# arcade_controls.net
KiCad netlist of a schematic drawn in EAGLE
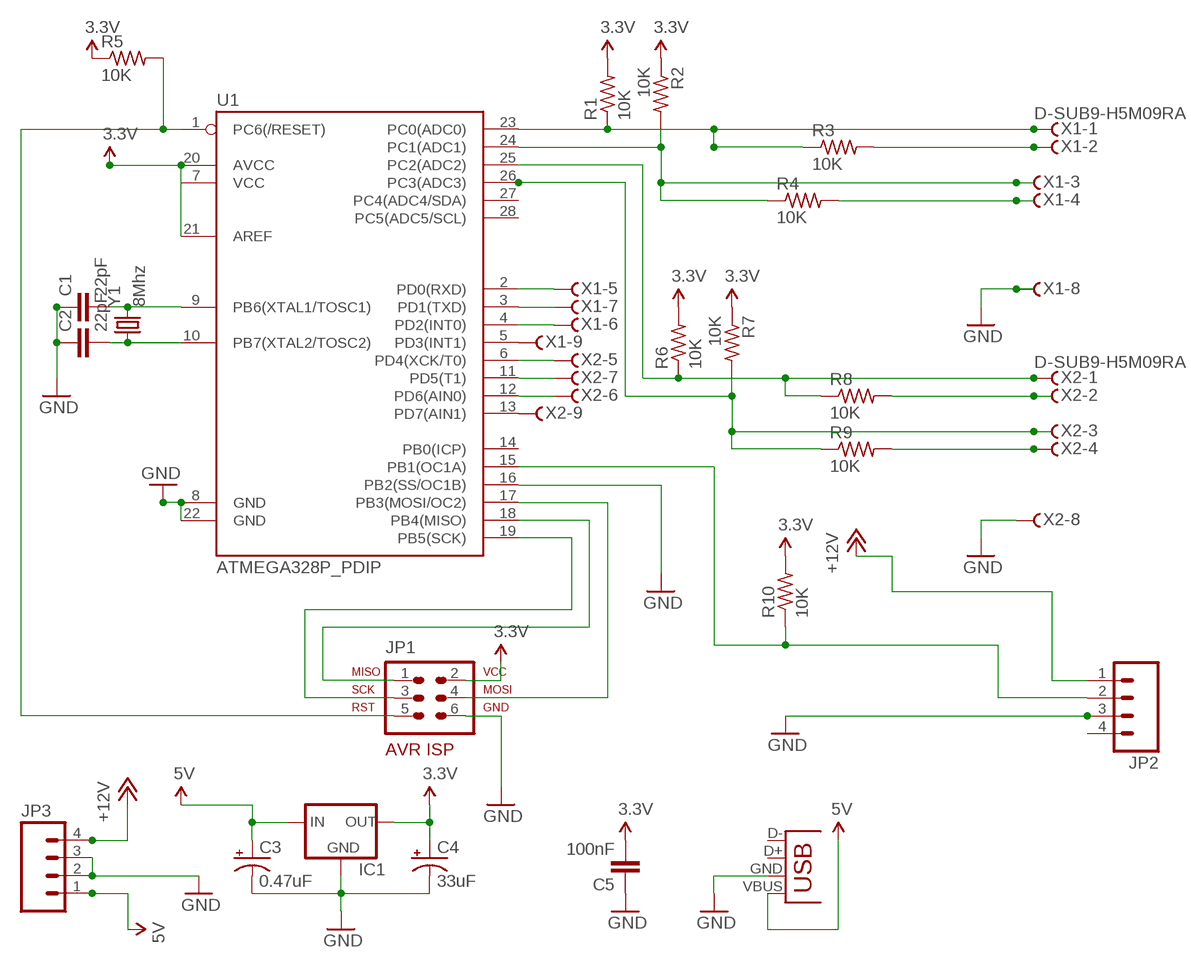
[diagram p0: schematic, sheet 1]

(export (version "E")
  (design (tool "Eeschema 10.0.6"))
  (components
    (comp (ref "C1")
      (value "22pF")
      (footprint "eagle-import:CAP-PTH-SMALL")
      (libsource (lib "eagle-import") (part "CAPPTH"))
    )
    (comp (ref "C2")
      (value "22pF")
      (footprint "eagle-import:CAP-PTH-SMALL")
      (libsource (lib "eagle-import") (part "CAPPTH"))
    )
    (comp (ref "C3")
      (value "0.47uF")
      (footprint "eagle-import:CPOL-RADIAL-10UF-25V")
      (libsource (lib "eagle-import") (part "CAP_POLPTH2"))
    )
    (comp (ref "C4")
      (value "33uF")
      (footprint "eagle-import:CPOL-RADIAL-10UF-25V")
      (libsource (lib "eagle-import") (part "CAP_POLPTH2"))
    )
    (comp (ref "C5")
      (value "100nF")
      (footprint "eagle-import:CAP-PTH-SMALL")
      (libsource (lib "eagle-import") (part "CAPPTH"))
    )
    (comp (ref "IC1")
      (value "V_REG_78XXSIDE")
      (footprint "eagle-import:78XXL")
      (libsource (lib "eagle-import") (part "V_REG_78XXSIDE"))
    )
    (comp (ref "JP1")
      (value "AVR-ISP-6VERT")
      (footprint "eagle-import:AVR-ISP-6")
      (libsource (lib "eagle-import") (part "AVR-ISP-6VERT"))
    )
    (comp (ref "JP2")
      (value "M04LOCK")
      (footprint "eagle-import:1X04_LOCK")
      (libsource (lib "eagle-import") (part "M04LOCK"))
    )
    (comp (ref "JP3")
      (value "M04LOCK")
      (footprint "eagle-import:1X04_LOCK")
      (libsource (lib "eagle-import") (part "M04LOCK"))
    )
    (comp (ref "JP4")
      (value "USB-A-H")
      (footprint "eagle-import:USB-A-H")
      (libsource (lib "eagle-import") (part "USB-A-H"))
    )
    (comp (ref "R1")
      (value "10K")
      (footprint "eagle-import:0309_12")
      (libsource (lib "eagle-import") (part "R-US_0309/12"))
    )
    (comp (ref "R2")
      (value "10K")
      (footprint "eagle-import:0309_12")
      (libsource (lib "eagle-import") (part "R-US_0309/12"))
    )
    (comp (ref "R3")
      (value "10K")
      (footprint "eagle-import:0309_12")
      (libsource (lib "eagle-import") (part "R-US_0309/12"))
    )
    (comp (ref "R4")
      (value "10K")
      (footprint "eagle-import:0309_12")
      (libsource (lib "eagle-import") (part "R-US_0309/12"))
    )
    (comp (ref "R5")
      (value "10K")
      (footprint "eagle-import:0309_12")
      (libsource (lib "eagle-import") (part "R-US_0309/12"))
    )
    (comp (ref "R6")
      (value "10K")
      (footprint "eagle-import:0309_12")
      (libsource (lib "eagle-import") (part "R-US_0309/12"))
    )
    (comp (ref "R7")
      (value "10K")
      (footprint "eagle-import:0309_12")
      (libsource (lib "eagle-import") (part "R-US_0309/12"))
    )
    (comp (ref "R8")
      (value "10K")
      (footprint "eagle-import:0309_12")
      (libsource (lib "eagle-import") (part "R-US_0309/12"))
    )
    (comp (ref "R9")
      (value "10K")
      (footprint "eagle-import:0309_12")
      (libsource (lib "eagle-import") (part "R-US_0309/12"))
    )
    (comp (ref "R10")
      (value "10K")
      (footprint "eagle-import:0309_12")
      (libsource (lib "eagle-import") (part "R-US_0309/12"))
    )
    (comp (ref "U1")
      (value "ATMEGA328P_PDIP")
      (footprint "eagle-import:DIL28-3")
      (libsource (lib "eagle-import") (part "ATMEGA328P_PDIP"))
    )
    (comp (ref "X1")
      (value "D-SUB9-H5M09RA")
      (footprint "eagle-import:H5M09RA")
      (libsource (lib "eagle-import") (part "D-SUB9-H5M09RA"))
    )
    (comp (ref "X2")
      (value "D-SUB9-H5M09RA")
      (footprint "eagle-import:H5M09RA")
      (libsource (lib "eagle-import") (part "D-SUB9-H5M09RA"))
    )
    (comp (ref "Y1")
      (value "8Mhz")
      (footprint "eagle-import:HC49U-V")
      (libsource (lib "eagle-import") (part "CRYSTALHC49UV"))
    )
  )
  (nets
    (net (code "1") (name "+12V") (class "Default")
      (node (ref "JP2") (pin "1") (pinfunction "1_1") (pintype "passive"))
      (node (ref "JP3") (pin "4") (pinfunction "4_4") (pintype "passive"))
    )
    (net (code "2") (name "3.3V") (class "Default")
      (node (ref "C4") (pin "1") (pinfunction "+_1") (pintype "passive"))
      (node (ref "C5") (pin "2") (pinfunction "2_2") (pintype "passive"))
      (node (ref "IC1") (pin "OUT") (pinfunction "OUT_OUT") (pintype "output"))
      (node (ref "JP1") (pin "2") (pinfunction "2_2") (pintype "passive"))
      (node (ref "R1") (pin "2") (pinfunction "2_2") (pintype "passive"))
      (node (ref "R10") (pin "2") (pinfunction "2_2") (pintype "passive"))
      (node (ref "R2") (pin "1") (pinfunction "1_1") (pintype "passive"))
      (node (ref "R5") (pin "1") (pinfunction "1_1") (pintype "passive"))
      (node (ref "R6") (pin "2") (pinfunction "2_2") (pintype "passive"))
      (node (ref "R7") (pin "1") (pinfunction "1_1") (pintype "passive"))
      (node (ref "U1") (pin "20") (pinfunction "AVCC_20") (pintype "bidirectional"))
      (node (ref "U1") (pin "21") (pinfunction "AREF_21") (pintype "bidirectional"))
      (node (ref "U1") (pin "7") (pinfunction "VCC_7") (pintype "bidirectional"))
    )
    (net (code "3") (name "5V") (class "Default")
      (node (ref "C3") (pin "1") (pinfunction "+_1") (pintype "passive"))
      (node (ref "IC1") (pin "IN") (pinfunction "IN_IN") (pintype "input"))
      (node (ref "JP3") (pin "1") (pinfunction "1_1") (pintype "passive"))
      (node (ref "JP4") (pin "VBUS") (pinfunction "GND_VBUS") (pintype "bidirectional"))
    )
    (net (code "4") (name "GND") (class "Default")
      (node (ref "C1") (pin "1") (pinfunction "1_1") (pintype "passive"))
      (node (ref "C2") (pin "1") (pinfunction "1_1") (pintype "passive"))
      (node (ref "C3") (pin "2") (pinfunction "-_2") (pintype "passive"))
      (node (ref "C4") (pin "2") (pinfunction "-_2") (pintype "passive"))
      (node (ref "C5") (pin "1") (pinfunction "1_1") (pintype "passive"))
      (node (ref "IC1") (pin "GND") (pinfunction "GND_GND") (pintype "input"))
      (node (ref "JP1") (pin "6") (pinfunction "6_6") (pintype "passive"))
      (node (ref "JP2") (pin "3") (pinfunction "3_3") (pintype "passive"))
      (node (ref "JP3") (pin "2") (pinfunction "2_2") (pintype "passive"))
      (node (ref "JP3") (pin "3") (pinfunction "3_3") (pintype "passive"))
      (node (ref "JP4") (pin "GND") (pinfunction "VBUS_GND") (pintype "bidirectional"))
      (node (ref "U1") (pin "16") (pinfunction "PB2(SS/OC1B)_16") (pintype "bidirectional"))
      (node (ref "U1") (pin "22") (pinfunction "GND_22") (pintype "bidirectional"))
      (node (ref "U1") (pin "8") (pinfunction "GND_8") (pintype "bidirectional"))
      (node (ref "X1") (pin "8") (pinfunction "F_8") (pintype "passive"))
      (node (ref "X2") (pin "8") (pinfunction "F_8") (pintype "passive"))
    )
    (net (code "5") (name "Net-(U1-PB1(OC1A))") (class "Default")
      (node (ref "JP2") (pin "2") (pinfunction "2_2") (pintype "passive"))
      (node (ref "R10") (pin "1") (pinfunction "1_1") (pintype "passive"))
      (node (ref "U1") (pin "15") (pinfunction "PB1(OC1A)_15") (pintype "bidirectional"))
    )
    (net (code "6") (name "Net-(U1-PB3(MOSI{slash}OC2))") (class "Default")
      (node (ref "JP1") (pin "4") (pinfunction "4_4") (pintype "passive"))
      (node (ref "U1") (pin "17") (pinfunction "PB3(MOSI/OC2)_17") (pintype "bidirectional"))
    )
    (net (code "7") (name "Net-(U1-PB4(MISO))") (class "Default")
      (node (ref "JP1") (pin "1") (pinfunction "1_1") (pintype "passive"))
      (node (ref "U1") (pin "18") (pinfunction "PB4(MISO)_18") (pintype "bidirectional"))
    )
    (net (code "8") (name "Net-(U1-PB5(SCK))") (class "Default")
      (node (ref "JP1") (pin "3") (pinfunction "3_3") (pintype "passive"))
      (node (ref "U1") (pin "19") (pinfunction "PB5(SCK)_19") (pintype "bidirectional"))
    )
    (net (code "9") (name "Net-(U1-PB6(XTAL1{slash}TOSC1))") (class "Default")
      (node (ref "C1") (pin "2") (pinfunction "2_2") (pintype "passive"))
      (node (ref "U1") (pin "9") (pinfunction "PB6(XTAL1/TOSC1)_9") (pintype "bidirectional"))
      (node (ref "Y1") (pin "2") (pinfunction "2_2") (pintype "passive"))
    )
    (net (code "10") (name "Net-(U1-PB7(XTAL2{slash}TOSC2))") (class "Default")
      (node (ref "C2") (pin "2") (pinfunction "2_2") (pintype "passive"))
      (node (ref "U1") (pin "10") (pinfunction "PB7(XTAL2/TOSC2)_10") (pintype "bidirectional"))
      (node (ref "Y1") (pin "1") (pinfunction "1_1") (pintype "passive"))
    )
    (net (code "11") (name "Net-(U1-PC0(ADC0))") (class "Default")
      (node (ref "R1") (pin "1") (pinfunction "1_1") (pintype "passive"))
      (node (ref "R3") (pin "1") (pinfunction "1_1") (pintype "passive"))
      (node (ref "U1") (pin "23") (pinfunction "PC0(ADC0)_23") (pintype "bidirectional"))
      (node (ref "X1") (pin "1") (pinfunction "F_1") (pintype "passive"))
    )
    (net (code "12") (name "Net-(U1-PC1(ADC1))") (class "Default")
      (node (ref "R2") (pin "2") (pinfunction "2_2") (pintype "passive"))
      (node (ref "R4") (pin "1") (pinfunction "1_1") (pintype "passive"))
      (node (ref "U1") (pin "24") (pinfunction "PC1(ADC1)_24") (pintype "bidirectional"))
      (node (ref "X1") (pin "3") (pinfunction "F_3") (pintype "passive"))
    )
    (net (code "13") (name "Net-(U1-PC2(ADC2))") (class "Default")
      (node (ref "R6") (pin "1") (pinfunction "1_1") (pintype "passive"))
      (node (ref "R8") (pin "1") (pinfunction "1_1") (pintype "passive"))
      (node (ref "U1") (pin "25") (pinfunction "PC2(ADC2)_25") (pintype "bidirectional"))
      (node (ref "X2") (pin "1") (pinfunction "F_1") (pintype "passive"))
    )
    (net (code "14") (name "Net-(U1-PC3(ADC3))") (class "Default")
      (node (ref "R7") (pin "2") (pinfunction "2_2") (pintype "passive"))
      (node (ref "R9") (pin "1") (pinfunction "1_1") (pintype "passive"))
      (node (ref "U1") (pin "26") (pinfunction "PC3(ADC3)_26") (pintype "bidirectional"))
      (node (ref "X2") (pin "3") (pinfunction "F_3") (pintype "passive"))
    )
    (net (code "15") (name "Net-(U1-PC6({slash}RESET))") (class "Default")
      (node (ref "JP1") (pin "5") (pinfunction "5_5") (pintype "passive"))
      (node (ref "R5") (pin "2") (pinfunction "2_2") (pintype "passive"))
      (node (ref "U1") (pin "1") (pinfunction "PC6(/RESET)_1") (pintype "bidirectional"))
    )
    (net (code "16") (name "Net-(U1-PD0(RXD))") (class "Default")
      (node (ref "U1") (pin "2") (pinfunction "PD0(RXD)_2") (pintype "bidirectional"))
      (node (ref "X1") (pin "5") (pinfunction "F_5") (pintype "passive"))
    )
    (net (code "17") (name "Net-(U1-PD1(TXD))") (class "Default")
      (node (ref "U1") (pin "3") (pinfunction "PD1(TXD)_3") (pintype "bidirectional"))
      (node (ref "X1") (pin "7") (pinfunction "F_7") (pintype "passive"))
    )
    (net (code "18") (name "Net-(U1-PD2(INT0))") (class "Default")
      (node (ref "U1") (pin "4") (pinfunction "PD2(INT0)_4") (pintype "bidirectional"))
      (node (ref "X1") (pin "6") (pinfunction "F_6") (pintype "passive"))
    )
    (net (code "19") (name "Net-(U1-PD3(INT1))") (class "Default")
      (node (ref "U1") (pin "5") (pinfunction "PD3(INT1)_5") (pintype "bidirectional"))
      (node (ref "X1") (pin "9") (pinfunction "F_9") (pintype "passive"))
    )
    (net (code "20") (name "Net-(U1-PD4(XCK{slash}T0))") (class "Default")
      (node (ref "U1") (pin "6") (pinfunction "PD4(XCK/T0)_6") (pintype "bidirectional"))
      (node (ref "X2") (pin "5") (pinfunction "F_5") (pintype "passive"))
    )
    (net (code "21") (name "Net-(U1-PD5(T1))") (class "Default")
      (node (ref "U1") (pin "11") (pinfunction "PD5(T1)_11") (pintype "bidirectional"))
      (node (ref "X2") (pin "7") (pinfunction "F_7") (pintype "passive"))
    )
    (net (code "22") (name "Net-(U1-PD6(AIN0))") (class "Default")
      (node (ref "U1") (pin "12") (pinfunction "PD6(AIN0)_12") (pintype "bidirectional"))
      (node (ref "X2") (pin "6") (pinfunction "F_6") (pintype "passive"))
    )
    (net (code "23") (name "Net-(U1-PD7(AIN1))") (class "Default")
      (node (ref "U1") (pin "13") (pinfunction "PD7(AIN1)_13") (pintype "bidirectional"))
      (node (ref "X2") (pin "9") (pinfunction "F_9") (pintype "passive"))
    )
    (net (code "24") (name "Net-(X1B-F)") (class "Default")
      (node (ref "R3") (pin "2") (pinfunction "2_2") (pintype "passive"))
      (node (ref "X1") (pin "2") (pinfunction "F_2") (pintype "passive"))
    )
    (net (code "25") (name "Net-(X1D-F)") (class "Default")
      (node (ref "R4") (pin "2") (pinfunction "2_2") (pintype "passive"))
      (node (ref "X1") (pin "4") (pinfunction "F_4") (pintype "passive"))
    )
    (net (code "26") (name "Net-(X2B-F)") (class "Default")
      (node (ref "R8") (pin "2") (pinfunction "2_2") (pintype "passive"))
      (node (ref "X2") (pin "2") (pinfunction "F_2") (pintype "passive"))
    )
    (net (code "27") (name "Net-(X2D-F)") (class "Default")
      (node (ref "R9") (pin "2") (pinfunction "2_2") (pintype "passive"))
      (node (ref "X2") (pin "4") (pinfunction "F_4") (pintype "passive"))
    )
    (net (code "28") (name "unconnected-(JP2-Pad4)") (class "Default")
      (node (ref "JP2") (pin "4") (pinfunction "4_4") (pintype "passive"))
    )
    (net (code "29") (name "unconnected-(JP4-D+-PadD-)") (class "Default")
      (node (ref "JP4") (pin "D-") (pinfunction "D+_D-") (pintype "bidirectional"))
    )
    (net (code "30") (name "unconnected-(JP4-D--PadD+)") (class "Default")
      (node (ref "JP4") (pin "D+") (pinfunction "D-_D+") (pintype "bidirectional"))
    )
    (net (code "31") (name "unconnected-(U1-PB0(ICP)-Pad14)") (class "Default")
      (node (ref "U1") (pin "14") (pinfunction "PB0(ICP)_14") (pintype "bidirectional"))
    )
    (net (code "32") (name "unconnected-(U1-PC4(ADC4{slash}SDA)-Pad27)") (class "Default")
      (node (ref "U1") (pin "27") (pinfunction "PC4(ADC4/SDA)_27") (pintype "bidirectional"))
    )
    (net (code "33") (name "unconnected-(U1-PC5(ADC5{slash}SCL)-Pad28)") (class "Default")
      (node (ref "U1") (pin "28") (pinfunction "PC5(ADC5/SCL)_28") (pintype "bidirectional"))
    )
  )
)
